# USB_Power_3V3_Regulator.net
KiCad netlist of a schematic drawn in Altium Designer
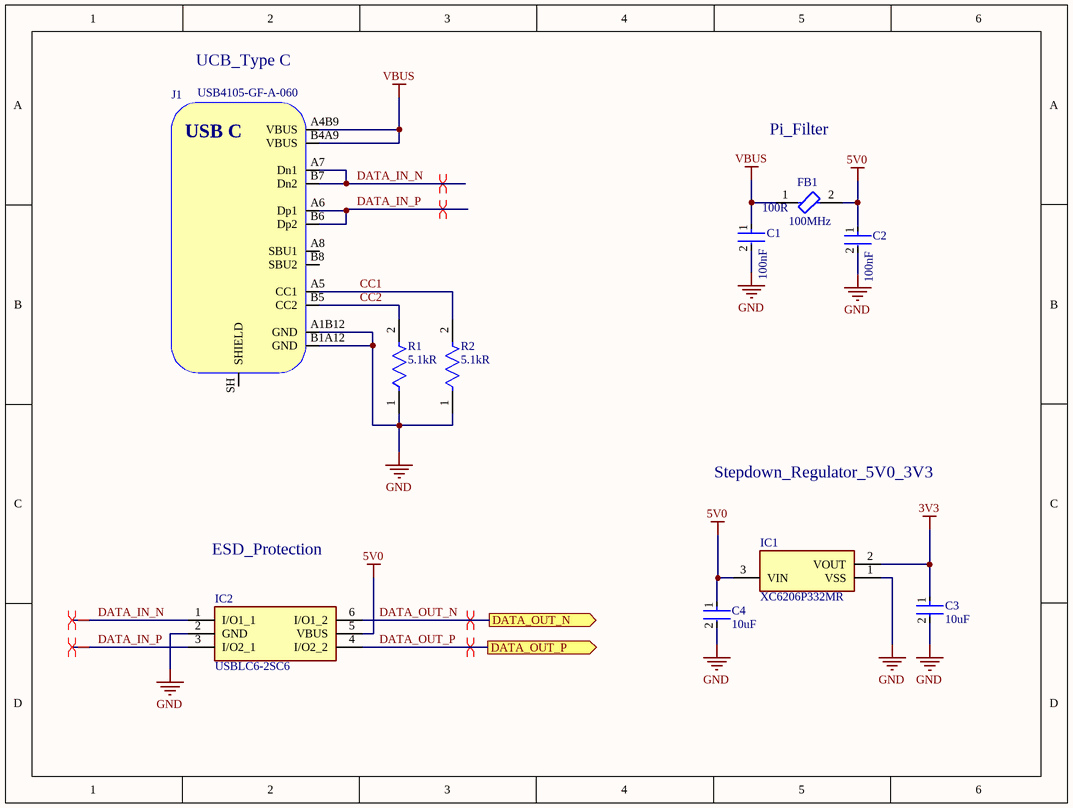
[diagram p0: USB_Power_3V3_Regulator.SchDoc]

(export (version "E")
  (design (tool "Eeschema 10.0.6"))
  (components
    (comp (ref "C1")
      (value "CL05A104KP5NNNC")
      (footprint "FP-CL46-IPC_C")
      (description "Cap Ceramic 100nF 10V X5R ±10% SMD 0402 +85°C Paper T/R")
      (fields (field (name "CAPACITANCE") "100nF") (field (name "TOLERANCE") "10%"))
      (libsource (lib "Altium Content Vault") (part "b4654b650e69147ec39a6b967a45e02"))
    )
    (comp (ref "C2")
      (value "CL05A104KP5NNNC")
      (footprint "FP-CL46-IPC_C")
      (description "Cap Ceramic 100nF 10V X5R ±10% SMD 0402 +85°C Paper T/R")
      (fields (field (name "CAPACITANCE") "100nF") (field (name "TOLERANCE") "10%"))
      (libsource (lib "Altium Content Vault") (part "b4654b650e69147ec39a6b967a45e02"))
    )
    (comp (ref "C3")
      (value "1206ZD106KAT2A")
      (footprint "FP-1206-L_3_2_0_2-W_1_6_0-IPC_A")
      (description "General Purpose Ceramic Capacitor, 1206, 10uF, 10%, X5R, 15%, 10V")
      (fields
        (field (name "TOLERANCE") "10%")
        (field (name "VOLTAGE") "10V")
        (field (name "CAPACITANCE") "10uF")
      )
      (libsource (lib "Altium Content Vault") (part "02cd4be3c70576c341d710602a673aa"))
    )
    (comp (ref "C4")
      (value "1206ZD106KAT2A")
      (footprint "FP-1206-L_3_2_0_2-W_1_6_0-IPC_A")
      (description "General Purpose Ceramic Capacitor, 1206, 10uF, 10%, X5R, 15%, 10V")
      (fields
        (field (name "TOLERANCE") "10%")
        (field (name "VOLTAGE") "10V")
        (field (name "CAPACITANCE") "10uF")
      )
      (libsource (lib "Altium Content Vault") (part "02cd4be3c70576c341d710602a673aa"))
    )
    (comp (ref "FB1")
      (value "BLM18EG101TN1D")
      (footprint "FP-BLM18-0_15-t0_5-MFG")
      (description "Chip Ferrite Bead, 0603, 100Ω @ 100MHz, 25%, 0.045Ω, 2A")
      (fields
        (field (name "TOLERANCE") "25%")
        (field (name "IMPEDANCE") "100R")
        (field (name "TEST FREQUENCY") "100MHz")
      )
      (libsource (lib "Altium Content Vault") (part "5f30dd21d616792df468990f7003faa"))
    )
    (comp (ref "IC1")
      (value "XC6206P332MR")
      (footprint "SOT95P280X130-3N")
      (description "Integrated Circuit")
      (libsource (lib "XC6206P332MR") (part "XC6206P332MR"))
    )
    (comp (ref "IC2")
      (value "USBLC6-2SC6")
      (footprint "SOT95P280X145-6N")
      (description "Integrated Circuit")
      (fields (field (name "MOUSER PART NUMBER") "511-USBLC6-2SC6"))
      (libsource (lib "USBLC6-2SC6") (part "USBLC6-2SC6"))
    )
    (comp (ref "J1")
      (value "USB4105-GF-A-060")
      (footprint "USB4105-GF-A-060")
      (description "USB Connector Type C SMT 12 Pin")
      (fields (field (name "MANUFACTURER") "GCT"))
      (libsource (lib "Schematic-Lib-PhilsLab") (part "USB4105-GF-A-060"))
    )
    (comp (ref "R1")
      (value "CRCW04025K10FKED")
      (footprint "FP-CRCW0402-e3-IPC_A")
      (description "RES Thick Film, 5.1kΩ, 1%, 0.063W, 100ppm/°C, 0402")
      (fields (field (name "TOLERANCE") "1%") (field (name "RESISTANCE") "5.1kR"))
      (libsource (lib "Altium Content Vault") (part "1029c3af85768c4190bb7ad29bc67b5"))
    )
    (comp (ref "R2")
      (value "CRCW04025K10FKED")
      (footprint "FP-CRCW0402-e3-IPC_A")
      (description "RES Thick Film, 5.1kΩ, 1%, 0.063W, 100ppm/°C, 0402")
      (fields (field (name "TOLERANCE") "1%") (field (name "RESISTANCE") "5.1kR"))
      (libsource (lib "Altium Content Vault") (part "1029c3af85768c4190bb7ad29bc67b5"))
    )
  )
  (nets
    (net (code "1") (name "/CC1") (class "Default")
      (node (ref "J1") (pin "A5") (pinfunction "CC1_A5") (pintype "passive"))
      (node (ref "R2") (pin "2") (pinfunction "2_2") (pintype "passive"))
    )
    (net (code "2") (name "/CC2") (class "Default")
      (node (ref "J1") (pin "B5") (pinfunction "CC2_B5") (pintype "passive"))
      (node (ref "R1") (pin "2") (pinfunction "2_2") (pintype "passive"))
    )
    (net (code "3") (name "/DATA_IN_N") (class "Default")
      (node (ref "IC2") (pin "1") (pinfunction "I/O1_1_1") (pintype "passive"))
      (node (ref "J1") (pin "A7") (pinfunction "Dn1_A7") (pintype "passive"))
      (node (ref "J1") (pin "B7") (pinfunction "Dn2_B7") (pintype "passive"))
    )
    (net (code "4") (name "/DATA_IN_P") (class "Default")
      (node (ref "IC2") (pin "3") (pinfunction "I/O2_1_3") (pintype "passive"))
      (node (ref "J1") (pin "A6") (pinfunction "Dp1_A6") (pintype "passive"))
      (node (ref "J1") (pin "B6") (pinfunction "Dp2_B6") (pintype "passive"))
    )
    (net (code "5") (name "/DATA_OUT_N") (class "Default")
      (node (ref "IC2") (pin "6") (pinfunction "I/O1_2_6") (pintype "passive"))
    )
    (net (code "6") (name "/DATA_OUT_P") (class "Default")
      (node (ref "IC2") (pin "4") (pinfunction "I/O2_2_4") (pintype "passive"))
    )
    (net (code "7") (name "3V3") (class "Default")
      (node (ref "C3") (pin "1") (pinfunction "1_1") (pintype "passive"))
      (node (ref "IC1") (pin "2") (pinfunction "VOUT_2") (pintype "passive"))
    )
    (net (code "8") (name "5V0") (class "Default")
      (node (ref "C2") (pin "1") (pinfunction "1_1") (pintype "passive"))
      (node (ref "C4") (pin "1") (pinfunction "1_1") (pintype "passive"))
      (node (ref "FB1") (pin "2") (pinfunction "2_2") (pintype "passive"))
      (node (ref "IC1") (pin "3") (pinfunction "VIN_3") (pintype "passive"))
      (node (ref "IC2") (pin "5") (pinfunction "VBUS_5") (pintype "passive"))
    )
    (net (code "9") (name "GND") (class "Default")
      (node (ref "C1") (pin "2") (pinfunction "2_2") (pintype "passive"))
      (node (ref "C2") (pin "2") (pinfunction "2_2") (pintype "passive"))
      (node (ref "C3") (pin "2") (pinfunction "2_2") (pintype "passive"))
      (node (ref "C4") (pin "2") (pinfunction "2_2") (pintype "passive"))
      (node (ref "IC1") (pin "1") (pinfunction "VSS_1") (pintype "passive"))
      (node (ref "IC2") (pin "2") (pinfunction "GND_2") (pintype "passive"))
      (node (ref "J1") (pin "A1B12") (pinfunction "GND_A1B12") (pintype "passive"))
      (node (ref "J1") (pin "B1A12") (pinfunction "GND_B1A12") (pintype "passive"))
      (node (ref "R1") (pin "1") (pinfunction "1_1") (pintype "passive"))
      (node (ref "R2") (pin "1") (pinfunction "1_1") (pintype "passive"))
    )
    (net (code "10") (name "VBUS") (class "Default")
      (node (ref "C1") (pin "1") (pinfunction "1_1") (pintype "passive"))
      (node (ref "FB1") (pin "1") (pinfunction "1_1") (pintype "passive"))
      (node (ref "J1") (pin "A4B9") (pinfunction "VBUS_A4B9") (pintype "passive"))
      (node (ref "J1") (pin "B4A9") (pinfunction "VBUS_B4A9") (pintype "passive"))
    )
    (net (code "11") (name "unconnected-(J1-SBU1-PadA8)") (class "Default")
      (node (ref "J1") (pin "A8") (pinfunction "SBU1_A8") (pintype "passive"))
    )
    (net (code "12") (name "unconnected-(J1-SBU2-PadB8)") (class "Default")
      (node (ref "J1") (pin "B8") (pinfunction "SBU2_B8") (pintype "passive"))
    )
    (net (code "13") (name "unconnected-(J1-SHIELD-PadSH)") (class "Default")
      (node (ref "J1") (pin "SH") (pinfunction "SHIELD_SH") (pintype "passive"))
    )
  )
)
